# CongSuat_SCH.net
KiCad netlist of a schematic drawn in Altium Designer
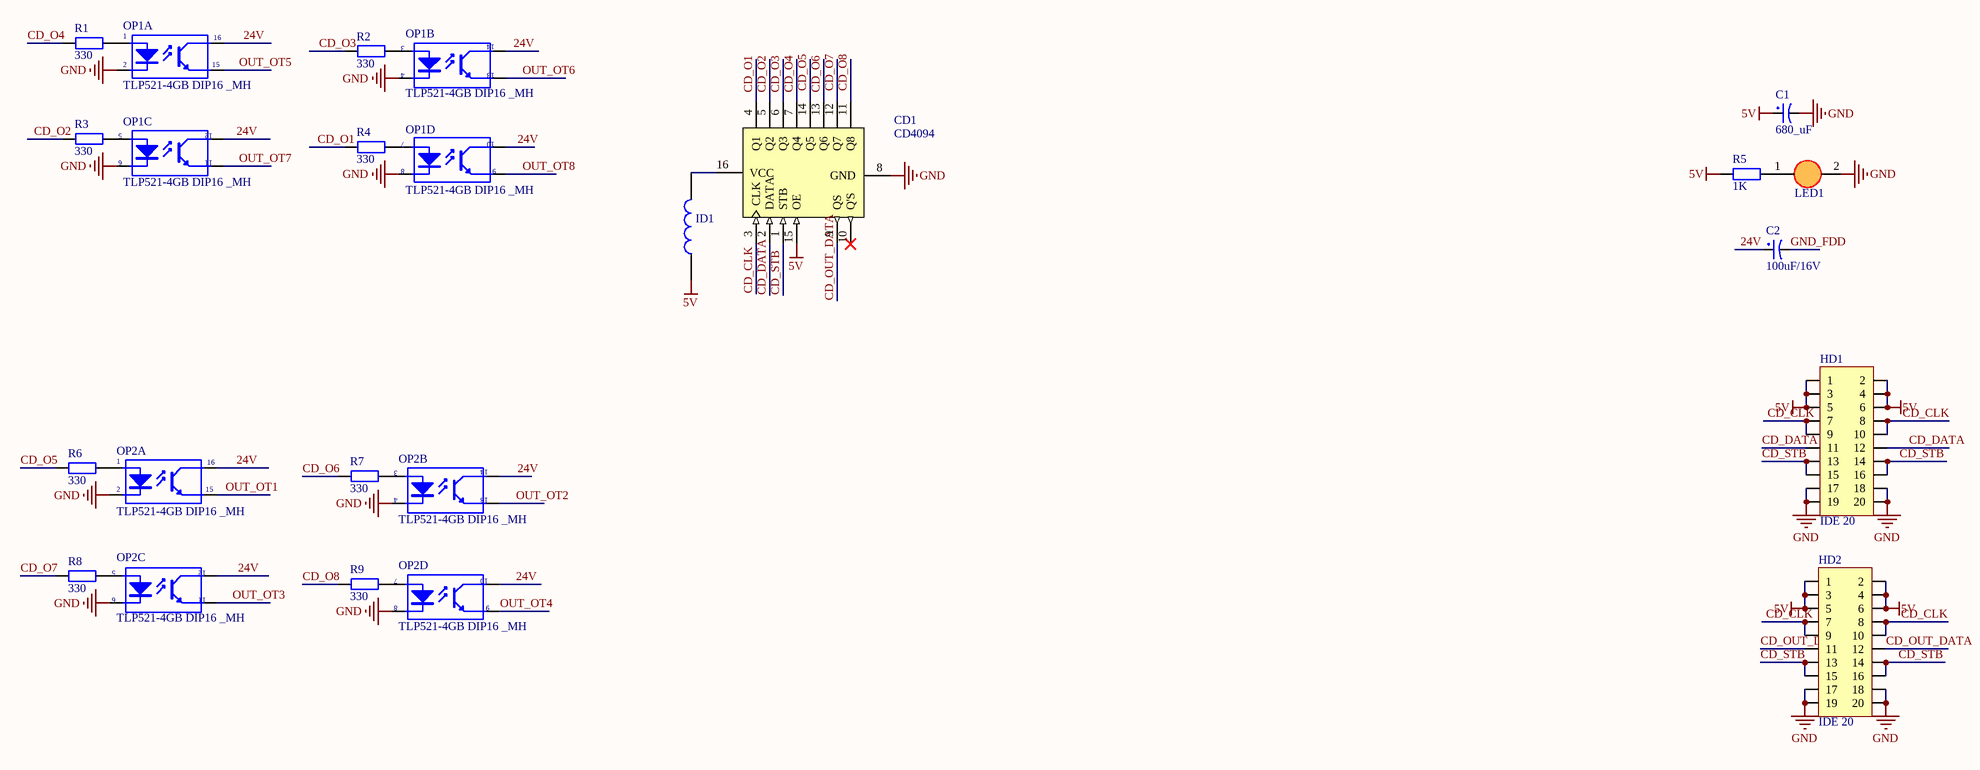
[diagram p0: CongSuat_SCH.SchDoc]

(export (version "E")
  (design (tool "Eeschema 10.0.6"))
  (components
    (comp (ref "C1")
      (value "680_uF")
      (footprint "TU_HOA(100uF/35V - 470uF/16V)")
      (description "TU_HOA_680_uF_25V")
      (libsource (lib "MH_DA_THU_VIEN_ALTIUM_19112016") (part "TU_HOA_680_uF_25V_MH"))
    )
    (comp (ref "C2")
      (value "100uF/16V")
      (footprint "TU_HOA(100uF/35V - 470uF/16V)")
      (description "TU_HOA_100uF_50V")
      (libsource (lib "MH_DA_THU_VIEN_ALTIUM_19112016") (part "TU_HOA_100uF_50V_MH"))
    )
    (comp (ref "CD1")
      (value "CD4094")
      (footprint "DIP16")
      (libsource (lib "MH_DA_THU_VIEN_ALTIUM_19112016") (part "CD4094"))
    )
    (comp (ref "HD1")
      (value "IDE 20")
      (footprint "CABLE 20")
      (description "IDE header 20P")
      (libsource (lib "MH_DA_THU_VIEN_ALTIUM_19112016") (part "IDE 20"))
    )
    (comp (ref "HD2")
      (value "IDE 20")
      (footprint "CABLE 20")
      (description "IDE header 20P")
      (libsource (lib "MH_DA_THU_VIEN_ALTIUM_19112016") (part "IDE 20"))
    )
    (comp (ref "ID1")
      (value "Inductor 0805_MH")
      (footprint "TU_SMD_0805")
      (description "cuon cam 0805")
      (libsource (lib "MH_DA_THU_VIEN_ALTIUM_19112016") (part "Inductor 0805_MH"))
    )
    (comp (ref "LED1")
      (value "LED3")
      (footprint "LED 3mm Do")
      (description "LED 3mm")
      (libsource (lib "MH_DA_THU_VIEN_ALTIUM_19112016") (part "LED 3mm_MH"))
    )
    (comp (ref "OP1")
      (value "TLP521-4GB DIP16 _MH")
      (footprint "DIP16")
      (libsource (lib "MH_DA_THU_VIEN_ALTIUM_19112016") (part "TLP521-4GB DIP16 _MH"))
    )
    (comp (ref "OP2")
      (value "TLP521-4GB DIP16 _MH")
      (footprint "DIP16")
      (libsource (lib "MH_DA_THU_VIEN_ALTIUM_19112016") (part "TLP521-4GB DIP16 _MH"))
    )
    (comp (ref "R1")
      (value "330")
      (footprint "Tro SMD 0805")
      (description "TRO_SMD_0805")
      (libsource (lib "MH_DA_THU_VIEN_ALTIUM_19112016") (part "TRO_SMD_0805_MH"))
    )
    (comp (ref "R2")
      (value "330")
      (footprint "Tro SMD 0805")
      (description "TRO_SMD_0805")
      (libsource (lib "MH_DA_THU_VIEN_ALTIUM_19112016") (part "TRO_SMD_0805_MH"))
    )
    (comp (ref "R3")
      (value "330")
      (footprint "Tro SMD 0805")
      (description "TRO_SMD_0805")
      (libsource (lib "MH_DA_THU_VIEN_ALTIUM_19112016") (part "TRO_SMD_0805_MH"))
    )
    (comp (ref "R4")
      (value "330")
      (footprint "Tro SMD 0805")
      (description "TRO_SMD_0805")
      (libsource (lib "MH_DA_THU_VIEN_ALTIUM_19112016") (part "TRO_SMD_0805_MH"))
    )
    (comp (ref "R5")
      (value "1K")
      (footprint "Tro SMD 0805")
      (description "TRO_SMD_0805")
      (libsource (lib "MH_DA_THU_VIEN_ALTIUM_19112016") (part "TRO_SMD_0805_MH"))
    )
    (comp (ref "R6")
      (value "330")
      (footprint "Tro SMD 0805")
      (description "TRO_SMD_0805")
      (libsource (lib "MH_DA_THU_VIEN_ALTIUM_19112016") (part "TRO_SMD_0805_MH"))
    )
    (comp (ref "R7")
      (value "330")
      (footprint "Tro SMD 0805")
      (description "TRO_SMD_0805")
      (libsource (lib "MH_DA_THU_VIEN_ALTIUM_19112016") (part "TRO_SMD_0805_MH"))
    )
    (comp (ref "R8")
      (value "330")
      (footprint "Tro SMD 0805")
      (description "TRO_SMD_0805")
      (libsource (lib "MH_DA_THU_VIEN_ALTIUM_19112016") (part "TRO_SMD_0805_MH"))
    )
    (comp (ref "R9")
      (value "330")
      (footprint "Tro SMD 0805")
      (description "TRO_SMD_0805")
      (libsource (lib "MH_DA_THU_VIEN_ALTIUM_19112016") (part "TRO_SMD_0805_MH"))
    )
  )
  (nets
    (net (code "1") (name "/24V") (class "Default")
      (node (ref "C2") (pin "1") (pinfunction "1_1") (pintype "passive"))
      (node (ref "OP1") (pin "10") (pinfunction "C_10") (pintype "passive"))
      (node (ref "OP1") (pin "12") (pinfunction "C_12") (pintype "passive"))
      (node (ref "OP1") (pin "14") (pinfunction "C_14") (pintype "passive"))
      (node (ref "OP1") (pin "16") (pinfunction "C_16") (pintype "passive"))
      (node (ref "OP2") (pin "10") (pinfunction "C_10") (pintype "passive"))
      (node (ref "OP2") (pin "12") (pinfunction "C_12") (pintype "passive"))
      (node (ref "OP2") (pin "14") (pinfunction "C_14") (pintype "passive"))
      (node (ref "OP2") (pin "16") (pinfunction "C_16") (pintype "passive"))
    )
    (net (code "2") (name "/CD_CLK") (class "Default")
      (node (ref "CD1") (pin "3") (pinfunction "CLK_3") (pintype "input"))
      (node (ref "HD1") (pin "10") (pinfunction "10_10") (pintype "passive"))
      (node (ref "HD1") (pin "7") (pinfunction "7_7") (pintype "passive"))
      (node (ref "HD1") (pin "8") (pinfunction "8_8") (pintype "passive"))
      (node (ref "HD1") (pin "9") (pinfunction "9_9") (pintype "passive"))
      (node (ref "HD2") (pin "10") (pinfunction "10_10") (pintype "passive"))
      (node (ref "HD2") (pin "7") (pinfunction "7_7") (pintype "passive"))
      (node (ref "HD2") (pin "8") (pinfunction "8_8") (pintype "passive"))
      (node (ref "HD2") (pin "9") (pinfunction "9_9") (pintype "passive"))
    )
    (net (code "3") (name "/CD_DATA") (class "Default")
      (node (ref "CD1") (pin "2") (pinfunction "DATA_2") (pintype "input"))
      (node (ref "HD1") (pin "11") (pinfunction "11_11") (pintype "passive"))
      (node (ref "HD1") (pin "12") (pinfunction "12_12") (pintype "passive"))
    )
    (net (code "4") (name "/CD_O1") (class "Default")
      (node (ref "CD1") (pin "4") (pinfunction "Q1_4") (pintype "tri_state"))
      (node (ref "R4") (pin "1") (pinfunction "1_1") (pintype "passive"))
    )
    (net (code "5") (name "/CD_O2") (class "Default")
      (node (ref "CD1") (pin "5") (pinfunction "Q2_5") (pintype "tri_state"))
      (node (ref "R3") (pin "1") (pinfunction "1_1") (pintype "passive"))
    )
    (net (code "6") (name "/CD_O3") (class "Default")
      (node (ref "CD1") (pin "6") (pinfunction "Q3_6") (pintype "tri_state"))
      (node (ref "R2") (pin "1") (pinfunction "1_1") (pintype "passive"))
    )
    (net (code "7") (name "/CD_O4") (class "Default")
      (node (ref "CD1") (pin "7") (pinfunction "Q4_7") (pintype "tri_state"))
      (node (ref "R1") (pin "1") (pinfunction "1_1") (pintype "passive"))
    )
    (net (code "8") (name "/CD_O5") (class "Default")
      (node (ref "CD1") (pin "14") (pinfunction "Q5_14") (pintype "tri_state"))
      (node (ref "R6") (pin "1") (pinfunction "1_1") (pintype "passive"))
    )
    (net (code "9") (name "/CD_O6") (class "Default")
      (node (ref "CD1") (pin "13") (pinfunction "Q6_13") (pintype "tri_state"))
      (node (ref "R7") (pin "1") (pinfunction "1_1") (pintype "passive"))
    )
    (net (code "10") (name "/CD_O7") (class "Default")
      (node (ref "CD1") (pin "12") (pinfunction "Q7_12") (pintype "tri_state"))
      (node (ref "R8") (pin "1") (pinfunction "1_1") (pintype "passive"))
    )
    (net (code "11") (name "/CD_O8") (class "Default")
      (node (ref "CD1") (pin "11") (pinfunction "Q8_11") (pintype "tri_state"))
      (node (ref "R9") (pin "1") (pinfunction "1_1") (pintype "passive"))
    )
    (net (code "12") (name "/CD_OUT_DATA") (class "Default")
      (node (ref "CD1") (pin "9") (pinfunction "QS_9") (pintype "output"))
      (node (ref "HD2") (pin "11") (pinfunction "11_11") (pintype "passive"))
      (node (ref "HD2") (pin "12") (pinfunction "12_12") (pintype "passive"))
    )
    (net (code "13") (name "/CD_STB") (class "Default")
      (node (ref "CD1") (pin "1") (pinfunction "STB_1") (pintype "input"))
      (node (ref "HD1") (pin "13") (pinfunction "13_13") (pintype "passive"))
      (node (ref "HD1") (pin "14") (pinfunction "14_14") (pintype "passive"))
      (node (ref "HD1") (pin "15") (pinfunction "15_15") (pintype "passive"))
      (node (ref "HD1") (pin "16") (pinfunction "16_16") (pintype "passive"))
      (node (ref "HD2") (pin "13") (pinfunction "13_13") (pintype "passive"))
      (node (ref "HD2") (pin "14") (pinfunction "14_14") (pintype "passive"))
      (node (ref "HD2") (pin "15") (pinfunction "15_15") (pintype "passive"))
      (node (ref "HD2") (pin "16") (pinfunction "16_16") (pintype "passive"))
    )
    (net (code "14") (name "/GND_FDD") (class "Default")
      (node (ref "C2") (pin "2") (pinfunction "2_2") (pintype "passive"))
    )
    (net (code "15") (name "/OUT_OT1") (class "Default")
      (node (ref "OP2") (pin "15") (pinfunction "E_15") (pintype "passive"))
    )
    (net (code "16") (name "/OUT_OT2") (class "Default")
      (node (ref "OP2") (pin "13") (pinfunction "E_13") (pintype "passive"))
    )
    (net (code "17") (name "/OUT_OT3") (class "Default")
      (node (ref "OP2") (pin "11") (pinfunction "E_11") (pintype "passive"))
    )
    (net (code "18") (name "/OUT_OT4") (class "Default")
      (node (ref "OP2") (pin "9") (pinfunction "E_9") (pintype "passive"))
    )
    (net (code "19") (name "/OUT_OT5") (class "Default")
      (node (ref "OP1") (pin "15") (pinfunction "E_15") (pintype "passive"))
    )
    (net (code "20") (name "/OUT_OT6") (class "Default")
      (node (ref "OP1") (pin "13") (pinfunction "E_13") (pintype "passive"))
    )
    (net (code "21") (name "/OUT_OT7") (class "Default")
      (node (ref "OP1") (pin "11") (pinfunction "E_11") (pintype "passive"))
    )
    (net (code "22") (name "/OUT_OT8") (class "Default")
      (node (ref "OP1") (pin "9") (pinfunction "E_9") (pintype "passive"))
    )
    (net (code "23") (name "5V") (class "Default")
      (node (ref "C1") (pin "1") (pinfunction "1_1") (pintype "passive"))
      (node (ref "CD1") (pin "15") (pinfunction "OE_15") (pintype "input"))
      (node (ref "HD1") (pin "1") (pinfunction "1_1") (pintype "passive"))
      (node (ref "HD1") (pin "2") (pinfunction "2_2") (pintype "passive"))
      (node (ref "HD1") (pin "3") (pinfunction "3_3") (pintype "passive"))
      (node (ref "HD1") (pin "4") (pinfunction "4_4") (pintype "passive"))
      (node (ref "HD1") (pin "5") (pinfunction "5_5") (pintype "passive"))
      (node (ref "HD1") (pin "6") (pinfunction "6_6") (pintype "passive"))
      (node (ref "HD2") (pin "1") (pinfunction "1_1") (pintype "passive"))
      (node (ref "HD2") (pin "2") (pinfunction "2_2") (pintype "passive"))
      (node (ref "HD2") (pin "3") (pinfunction "3_3") (pintype "passive"))
      (node (ref "HD2") (pin "4") (pinfunction "4_4") (pintype "passive"))
      (node (ref "HD2") (pin "5") (pinfunction "5_5") (pintype "passive"))
      (node (ref "HD2") (pin "6") (pinfunction "6_6") (pintype "passive"))
      (node (ref "ID1") (pin "1") (pinfunction "1_1") (pintype "passive"))
      (node (ref "R5") (pin "1") (pinfunction "1_1") (pintype "passive"))
    )
    (net (code "24") (name "GND") (class "Default")
      (node (ref "C1") (pin "2") (pinfunction "2_2") (pintype "passive"))
      (node (ref "CD1") (pin "8") (pinfunction "GND_8") (pintype "power_in"))
      (node (ref "HD1") (pin "17") (pinfunction "17_17") (pintype "passive"))
      (node (ref "HD1") (pin "18") (pinfunction "18_18") (pintype "passive"))
      (node (ref "HD1") (pin "19") (pinfunction "19_19") (pintype "passive"))
      (node (ref "HD1") (pin "20") (pinfunction "20_20") (pintype "passive"))
      (node (ref "HD2") (pin "17") (pinfunction "17_17") (pintype "passive"))
      (node (ref "HD2") (pin "18") (pinfunction "18_18") (pintype "passive"))
      (node (ref "HD2") (pin "19") (pinfunction "19_19") (pintype "passive"))
      (node (ref "HD2") (pin "20") (pinfunction "20_20") (pintype "passive"))
      (node (ref "LED1") (pin "2") (pinfunction "K_2") (pintype "passive"))
      (node (ref "OP1") (pin "2") (pinfunction "K_2") (pintype "passive"))
      (node (ref "OP1") (pin "4") (pinfunction "K_4") (pintype "passive"))
      (node (ref "OP1") (pin "6") (pinfunction "K_6") (pintype "passive"))
      (node (ref "OP1") (pin "8") (pinfunction "K_8") (pintype "passive"))
      (node (ref "OP2") (pin "2") (pinfunction "K_2") (pintype "passive"))
      (node (ref "OP2") (pin "4") (pinfunction "K_4") (pintype "passive"))
      (node (ref "OP2") (pin "6") (pinfunction "K_6") (pintype "passive"))
      (node (ref "OP2") (pin "8") (pinfunction "K_8") (pintype "passive"))
    )
    (net (code "25") (name "Net-(CD1-VCC)") (class "Default")
      (node (ref "CD1") (pin "16") (pinfunction "VCC_16") (pintype "power_in"))
      (node (ref "ID1") (pin "2") (pinfunction "2_2") (pintype "passive"))
    )
    (net (code "26") (name "Net-(LED1-A)") (class "Default")
      (node (ref "LED1") (pin "1") (pinfunction "A_1") (pintype "passive"))
      (node (ref "R5") (pin "2") (pinfunction "2_2") (pintype "passive"))
    )
    (net (code "27") (name "Net-(OP1A-A)") (class "Default")
      (node (ref "OP1") (pin "1") (pinfunction "A_1") (pintype "passive"))
      (node (ref "R1") (pin "2") (pinfunction "2_2") (pintype "passive"))
    )
    (net (code "28") (name "Net-(OP1B-A)") (class "Default")
      (node (ref "OP1") (pin "3") (pinfunction "A_3") (pintype "passive"))
      (node (ref "R2") (pin "2") (pinfunction "2_2") (pintype "passive"))
    )
    (net (code "29") (name "Net-(OP1C-A)") (class "Default")
      (node (ref "OP1") (pin "5") (pinfunction "A_5") (pintype "passive"))
      (node (ref "R3") (pin "2") (pinfunction "2_2") (pintype "passive"))
    )
    (net (code "30") (name "Net-(OP1D-A)") (class "Default")
      (node (ref "OP1") (pin "7") (pinfunction "A_7") (pintype "passive"))
      (node (ref "R4") (pin "2") (pinfunction "2_2") (pintype "passive"))
    )
    (net (code "31") (name "Net-(OP2A-A)") (class "Default")
      (node (ref "OP2") (pin "1") (pinfunction "A_1") (pintype "passive"))
      (node (ref "R6") (pin "2") (pinfunction "2_2") (pintype "passive"))
    )
    (net (code "32") (name "Net-(OP2B-A)") (class "Default")
      (node (ref "OP2") (pin "3") (pinfunction "A_3") (pintype "passive"))
      (node (ref "R7") (pin "2") (pinfunction "2_2") (pintype "passive"))
    )
    (net (code "33") (name "Net-(OP2C-A)") (class "Default")
      (node (ref "OP2") (pin "5") (pinfunction "A_5") (pintype "passive"))
      (node (ref "R8") (pin "2") (pinfunction "2_2") (pintype "passive"))
    )
    (net (code "34") (name "Net-(OP2D-A)") (class "Default")
      (node (ref "OP2") (pin "7") (pinfunction "A_7") (pintype "passive"))
      (node (ref "R9") (pin "2") (pinfunction "2_2") (pintype "passive"))
    )
    (net (code "35") (name "unconnected-(CD1-Q'S-Pad10)") (class "Default")
      (node (ref "CD1") (pin "10") (pinfunction "Q'S_10") (pintype "output+no_connect"))
    )
  )
)
